# main.net
KiCad netlist of a schematic drawn in EAGLE
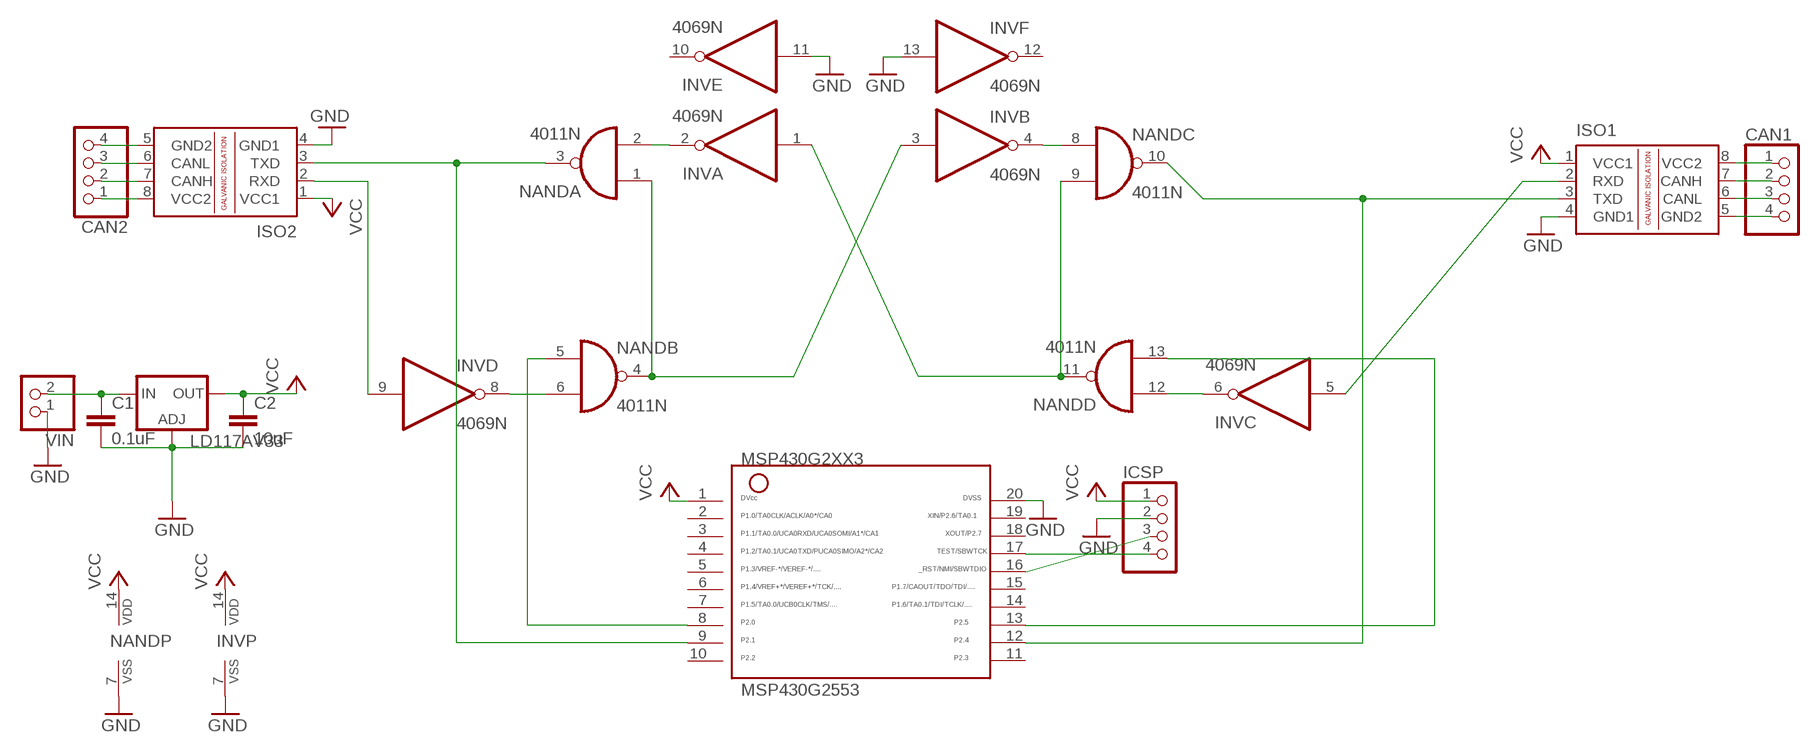
[diagram p0: schematic, sheet 1]

(export (version "E")
  (design (tool "Eeschema 10.0.6"))
  (components
    (comp (ref "C1")
      (value "0.1uF")
      (footprint "eagle-import:C025-024X044")
      (libsource (lib "eagle-import") (part "C-EU025-024X044"))
    )
    (comp (ref "C2")
      (value "10uF")
      (footprint "eagle-import:C025-024X044")
      (libsource (lib "eagle-import") (part "C-EU025-024X044"))
    )
    (comp (ref "CAN1")
      (value "PINHD-1X4")
      (footprint "eagle-import:1X04")
      (libsource (lib "eagle-import") (part "PINHD-1X4"))
    )
    (comp (ref "CAN2")
      (value "PINHD-1X4")
      (footprint "eagle-import:1X04")
      (libsource (lib "eagle-import") (part "PINHD-1X4"))
    )
    (comp (ref "ICSP")
      (value "PINHD-1X4")
      (footprint "eagle-import:1X04")
      (libsource (lib "eagle-import") (part "PINHD-1X4"))
    )
    (comp (ref "INV")
      (value "4069N")
      (footprint "eagle-import:DIL14")
      (libsource (lib "eagle-import") (part "4069N"))
    )
    (comp (ref "ISO1")
      (value "ISO1050DUB")
      (footprint "eagle-import:DUB-R-PDSO-G8")
      (fields (field (name "MPN") "ISO1050DUBR"))
      (libsource (lib "eagle-import") (part "ISO1050DUB"))
    )
    (comp (ref "ISO2")
      (value "ISO1050DUB")
      (footprint "eagle-import:DUB-R-PDSO-G8")
      (fields (field (name "MPN") "ISO1050DUBR"))
      (libsource (lib "eagle-import") (part "ISO1050DUB"))
    )
    (comp (ref "LD117AV33")
      (value "LD117AV33")
      (footprint "eagle-import:TO220L1")
      (libsource (lib "eagle-import") (part "LD117A?V33"))
    )
    (comp (ref "MSP430G2553")
      (value "G2XX3---N20")
      (footprint "eagle-import:N20")
      (libsource (lib "eagle-import") (part "G2XX3---N20"))
    )
    (comp (ref "NAND")
      (value "4011N")
      (footprint "eagle-import:DIL14")
      (libsource (lib "eagle-import") (part "4011N"))
    )
    (comp (ref "VIN")
      (value "PINHD-1X2")
      (footprint "eagle-import:1X02")
      (libsource (lib "eagle-import") (part "PINHD-1X2"))
    )
  )
  (nets
    (net (code "1") (name "GND") (class "Default")
      (node (ref "C1") (pin "2") (pinfunction "2_2") (pintype "passive"))
      (node (ref "C2") (pin "2") (pinfunction "2_2") (pintype "passive"))
      (node (ref "ICSP") (pin "2") (pinfunction "2_2") (pintype "passive"))
      (node (ref "INV") (pin "11") (pinfunction "I_11") (pintype "input"))
      (node (ref "INV") (pin "13") (pinfunction "I_13") (pintype "input"))
      (node (ref "INV") (pin "7") (pinfunction "VSS_7") (pintype "power_in"))
      (node (ref "ISO1") (pin "4") (pinfunction "GND1_4") (pintype "input"))
      (node (ref "ISO2") (pin "4") (pinfunction "GND1_4") (pintype "input"))
      (node (ref "LD117AV33") (pin "1") (pinfunction "ADJ_1") (pintype "input"))
      (node (ref "MSP430G2553") (pin "20") (pinfunction "20_20") (pintype "bidirectional"))
      (node (ref "NAND") (pin "7") (pinfunction "VSS_7") (pintype "power_in"))
      (node (ref "VIN") (pin "1") (pinfunction "1_1") (pintype "passive"))
    )
    (net (code "2") (name "Net-(ICSP-Pad3)") (class "Default")
      (node (ref "ICSP") (pin "3") (pinfunction "3_3") (pintype "passive"))
      (node (ref "MSP430G2553") (pin "16") (pinfunction "16_16") (pintype "bidirectional"))
    )
    (net (code "3") (name "Net-(ICSP-Pad4)") (class "Default")
      (node (ref "ICSP") (pin "4") (pinfunction "4_4") (pintype "passive"))
      (node (ref "MSP430G2553") (pin "17") (pinfunction "17_17") (pintype "bidirectional"))
    )
    (net (code "4") (name "Net-(INVA-I)") (class "Default")
      (node (ref "INV") (pin "1") (pinfunction "I_1") (pintype "input"))
      (node (ref "NAND") (pin "11") (pinfunction "O_11") (pintype "output"))
      (node (ref "NAND") (pin "9") (pinfunction "I1_9") (pintype "input"))
    )
    (net (code "5") (name "Net-(INVA-O)") (class "Default")
      (node (ref "INV") (pin "2") (pinfunction "O_2") (pintype "output"))
      (node (ref "NAND") (pin "2") (pinfunction "I1_2") (pintype "input"))
    )
    (net (code "6") (name "Net-(INVB-I)") (class "Default")
      (node (ref "INV") (pin "3") (pinfunction "I_3") (pintype "input"))
      (node (ref "NAND") (pin "1") (pinfunction "I0_1") (pintype "input"))
      (node (ref "NAND") (pin "4") (pinfunction "O_4") (pintype "output"))
    )
    (net (code "7") (name "Net-(INVB-O)") (class "Default")
      (node (ref "INV") (pin "4") (pinfunction "O_4") (pintype "output"))
      (node (ref "NAND") (pin "8") (pinfunction "I0_8") (pintype "input"))
    )
    (net (code "8") (name "Net-(INVC-I)") (class "Default")
      (node (ref "INV") (pin "5") (pinfunction "I_5") (pintype "input"))
      (node (ref "ISO1") (pin "2") (pinfunction "RXD_2") (pintype "input"))
    )
    (net (code "9") (name "Net-(INVC-O)") (class "Default")
      (node (ref "INV") (pin "6") (pinfunction "O_6") (pintype "output"))
      (node (ref "NAND") (pin "12") (pinfunction "I0_12") (pintype "input"))
    )
    (net (code "10") (name "Net-(INVD-I)") (class "Default")
      (node (ref "INV") (pin "9") (pinfunction "I_9") (pintype "input"))
      (node (ref "ISO2") (pin "2") (pinfunction "RXD_2") (pintype "input"))
    )
    (net (code "11") (name "Net-(INVD-O)") (class "Default")
      (node (ref "INV") (pin "8") (pinfunction "O_8") (pintype "output"))
      (node (ref "NAND") (pin "6") (pinfunction "I1_6") (pintype "input"))
    )
    (net (code "12") (name "Net-(ISO1-CANH)") (class "Default")
      (node (ref "CAN1") (pin "2") (pinfunction "2_2") (pintype "passive"))
      (node (ref "ISO1") (pin "7") (pinfunction "CANH_7") (pintype "input"))
    )
    (net (code "13") (name "Net-(ISO1-CANL)") (class "Default")
      (node (ref "CAN1") (pin "3") (pinfunction "3_3") (pintype "passive"))
      (node (ref "ISO1") (pin "6") (pinfunction "CANL_6") (pintype "input"))
    )
    (net (code "14") (name "Net-(ISO1-GND2)") (class "Default")
      (node (ref "CAN1") (pin "4") (pinfunction "4_4") (pintype "passive"))
      (node (ref "ISO1") (pin "5") (pinfunction "GND2_5") (pintype "input"))
    )
    (net (code "15") (name "Net-(ISO1-TXD)") (class "Default")
      (node (ref "ISO1") (pin "3") (pinfunction "TXD_3") (pintype "input"))
      (node (ref "MSP430G2553") (pin "12") (pinfunction "12_12") (pintype "bidirectional"))
      (node (ref "NAND") (pin "10") (pinfunction "O_10") (pintype "output"))
    )
    (net (code "16") (name "Net-(ISO1-VCC2)") (class "Default")
      (node (ref "CAN1") (pin "1") (pinfunction "1_1") (pintype "passive"))
      (node (ref "ISO1") (pin "8") (pinfunction "VCC2_8") (pintype "input"))
    )
    (net (code "17") (name "Net-(ISO2-CANH)") (class "Default")
      (node (ref "CAN2") (pin "2") (pinfunction "2_2") (pintype "passive"))
      (node (ref "ISO2") (pin "7") (pinfunction "CANH_7") (pintype "input"))
    )
    (net (code "18") (name "Net-(ISO2-CANL)") (class "Default")
      (node (ref "CAN2") (pin "3") (pinfunction "3_3") (pintype "passive"))
      (node (ref "ISO2") (pin "6") (pinfunction "CANL_6") (pintype "input"))
    )
    (net (code "19") (name "Net-(ISO2-GND2)") (class "Default")
      (node (ref "CAN2") (pin "4") (pinfunction "4_4") (pintype "passive"))
      (node (ref "ISO2") (pin "5") (pinfunction "GND2_5") (pintype "input"))
    )
    (net (code "20") (name "Net-(ISO2-TXD)") (class "Default")
      (node (ref "ISO2") (pin "3") (pinfunction "TXD_3") (pintype "input"))
      (node (ref "MSP430G2553") (pin "9") (pinfunction "9_9") (pintype "bidirectional"))
      (node (ref "NAND") (pin "3") (pinfunction "O_3") (pintype "output"))
    )
    (net (code "21") (name "Net-(ISO2-VCC2)") (class "Default")
      (node (ref "CAN2") (pin "1") (pinfunction "1_1") (pintype "passive"))
      (node (ref "ISO2") (pin "8") (pinfunction "VCC2_8") (pintype "input"))
    )
    (net (code "22") (name "Net-(LD117AV33-IN)") (class "Default")
      (node (ref "C1") (pin "1") (pinfunction "1_1") (pintype "passive"))
      (node (ref "LD117AV33") (pin "3") (pinfunction "IN_3") (pintype "input"))
      (node (ref "VIN") (pin "2") (pinfunction "2_2") (pintype "passive"))
    )
    (net (code "23") (name "Net-(NANDB-I0)") (class "Default")
      (node (ref "MSP430G2553") (pin "8") (pinfunction "8_8") (pintype "bidirectional"))
      (node (ref "NAND") (pin "5") (pinfunction "I0_5") (pintype "input"))
    )
    (net (code "24") (name "Net-(NANDD-I1)") (class "Default")
      (node (ref "MSP430G2553") (pin "13") (pinfunction "13_13") (pintype "bidirectional"))
      (node (ref "NAND") (pin "13") (pinfunction "I1_13") (pintype "input"))
    )
    (net (code "25") (name "VCC") (class "Default")
      (node (ref "C2") (pin "1") (pinfunction "1_1") (pintype "passive"))
      (node (ref "ICSP") (pin "1") (pinfunction "1_1") (pintype "passive"))
      (node (ref "INV") (pin "14") (pinfunction "VDD_14") (pintype "power_in"))
      (node (ref "ISO1") (pin "1") (pinfunction "VCC1_1") (pintype "input"))
      (node (ref "ISO2") (pin "1") (pinfunction "VCC1_1") (pintype "input"))
      (node (ref "LD117AV33") (pin "2") (pinfunction "OUT_2") (pintype "passive"))
      (node (ref "MSP430G2553") (pin "1") (pinfunction "1_1") (pintype "bidirectional"))
      (node (ref "NAND") (pin "14") (pinfunction "VDD_14") (pintype "power_in"))
    )
    (net (code "26") (name "unconnected-(INVE-O-Pad10)") (class "Default")
      (node (ref "INV") (pin "10") (pinfunction "O_10") (pintype "output"))
    )
    (net (code "27") (name "unconnected-(INVF-O-Pad12)") (class "Default")
      (node (ref "INV") (pin "12") (pinfunction "O_12") (pintype "output"))
    )
    (net (code "28") (name "unconnected-(MSP430G2553-Pad2)") (class "Default")
      (node (ref "MSP430G2553") (pin "2") (pinfunction "2_2") (pintype "bidirectional"))
    )
    (net (code "29") (name "unconnected-(MSP430G2553-Pad3)") (class "Default")
      (node (ref "MSP430G2553") (pin "3") (pinfunction "3_3") (pintype "bidirectional"))
    )
    (net (code "30") (name "unconnected-(MSP430G2553-Pad4)") (class "Default")
      (node (ref "MSP430G2553") (pin "4") (pinfunction "4_4") (pintype "bidirectional"))
    )
    (net (code "31") (name "unconnected-(MSP430G2553-Pad5)") (class "Default")
      (node (ref "MSP430G2553") (pin "5") (pinfunction "5_5") (pintype "bidirectional"))
    )
    (net (code "32") (name "unconnected-(MSP430G2553-Pad6)") (class "Default")
      (node (ref "MSP430G2553") (pin "6") (pinfunction "6_6") (pintype "bidirectional"))
    )
    (net (code "33") (name "unconnected-(MSP430G2553-Pad7)") (class "Default")
      (node (ref "MSP430G2553") (pin "7") (pinfunction "7_7") (pintype "bidirectional"))
    )
    (net (code "34") (name "unconnected-(MSP430G2553-Pad10)") (class "Default")
      (node (ref "MSP430G2553") (pin "10") (pinfunction "10_10") (pintype "bidirectional"))
    )
    (net (code "35") (name "unconnected-(MSP430G2553-Pad11)") (class "Default")
      (node (ref "MSP430G2553") (pin "11") (pinfunction "11_11") (pintype "bidirectional"))
    )
    (net (code "36") (name "unconnected-(MSP430G2553-Pad14)") (class "Default")
      (node (ref "MSP430G2553") (pin "14") (pinfunction "14_14") (pintype "bidirectional"))
    )
    (net (code "37") (name "unconnected-(MSP430G2553-Pad15)") (class "Default")
      (node (ref "MSP430G2553") (pin "15") (pinfunction "15_15") (pintype "bidirectional"))
    )
    (net (code "38") (name "unconnected-(MSP430G2553-Pad18)") (class "Default")
      (node (ref "MSP430G2553") (pin "18") (pinfunction "18_18") (pintype "bidirectional"))
    )
    (net (code "39") (name "unconnected-(MSP430G2553-Pad19)") (class "Default")
      (node (ref "MSP430G2553") (pin "19") (pinfunction "19_19") (pintype "bidirectional"))
    )
  )
)
